# amplifier-controller.net
KiCad netlist of a schematic drawn in EAGLE
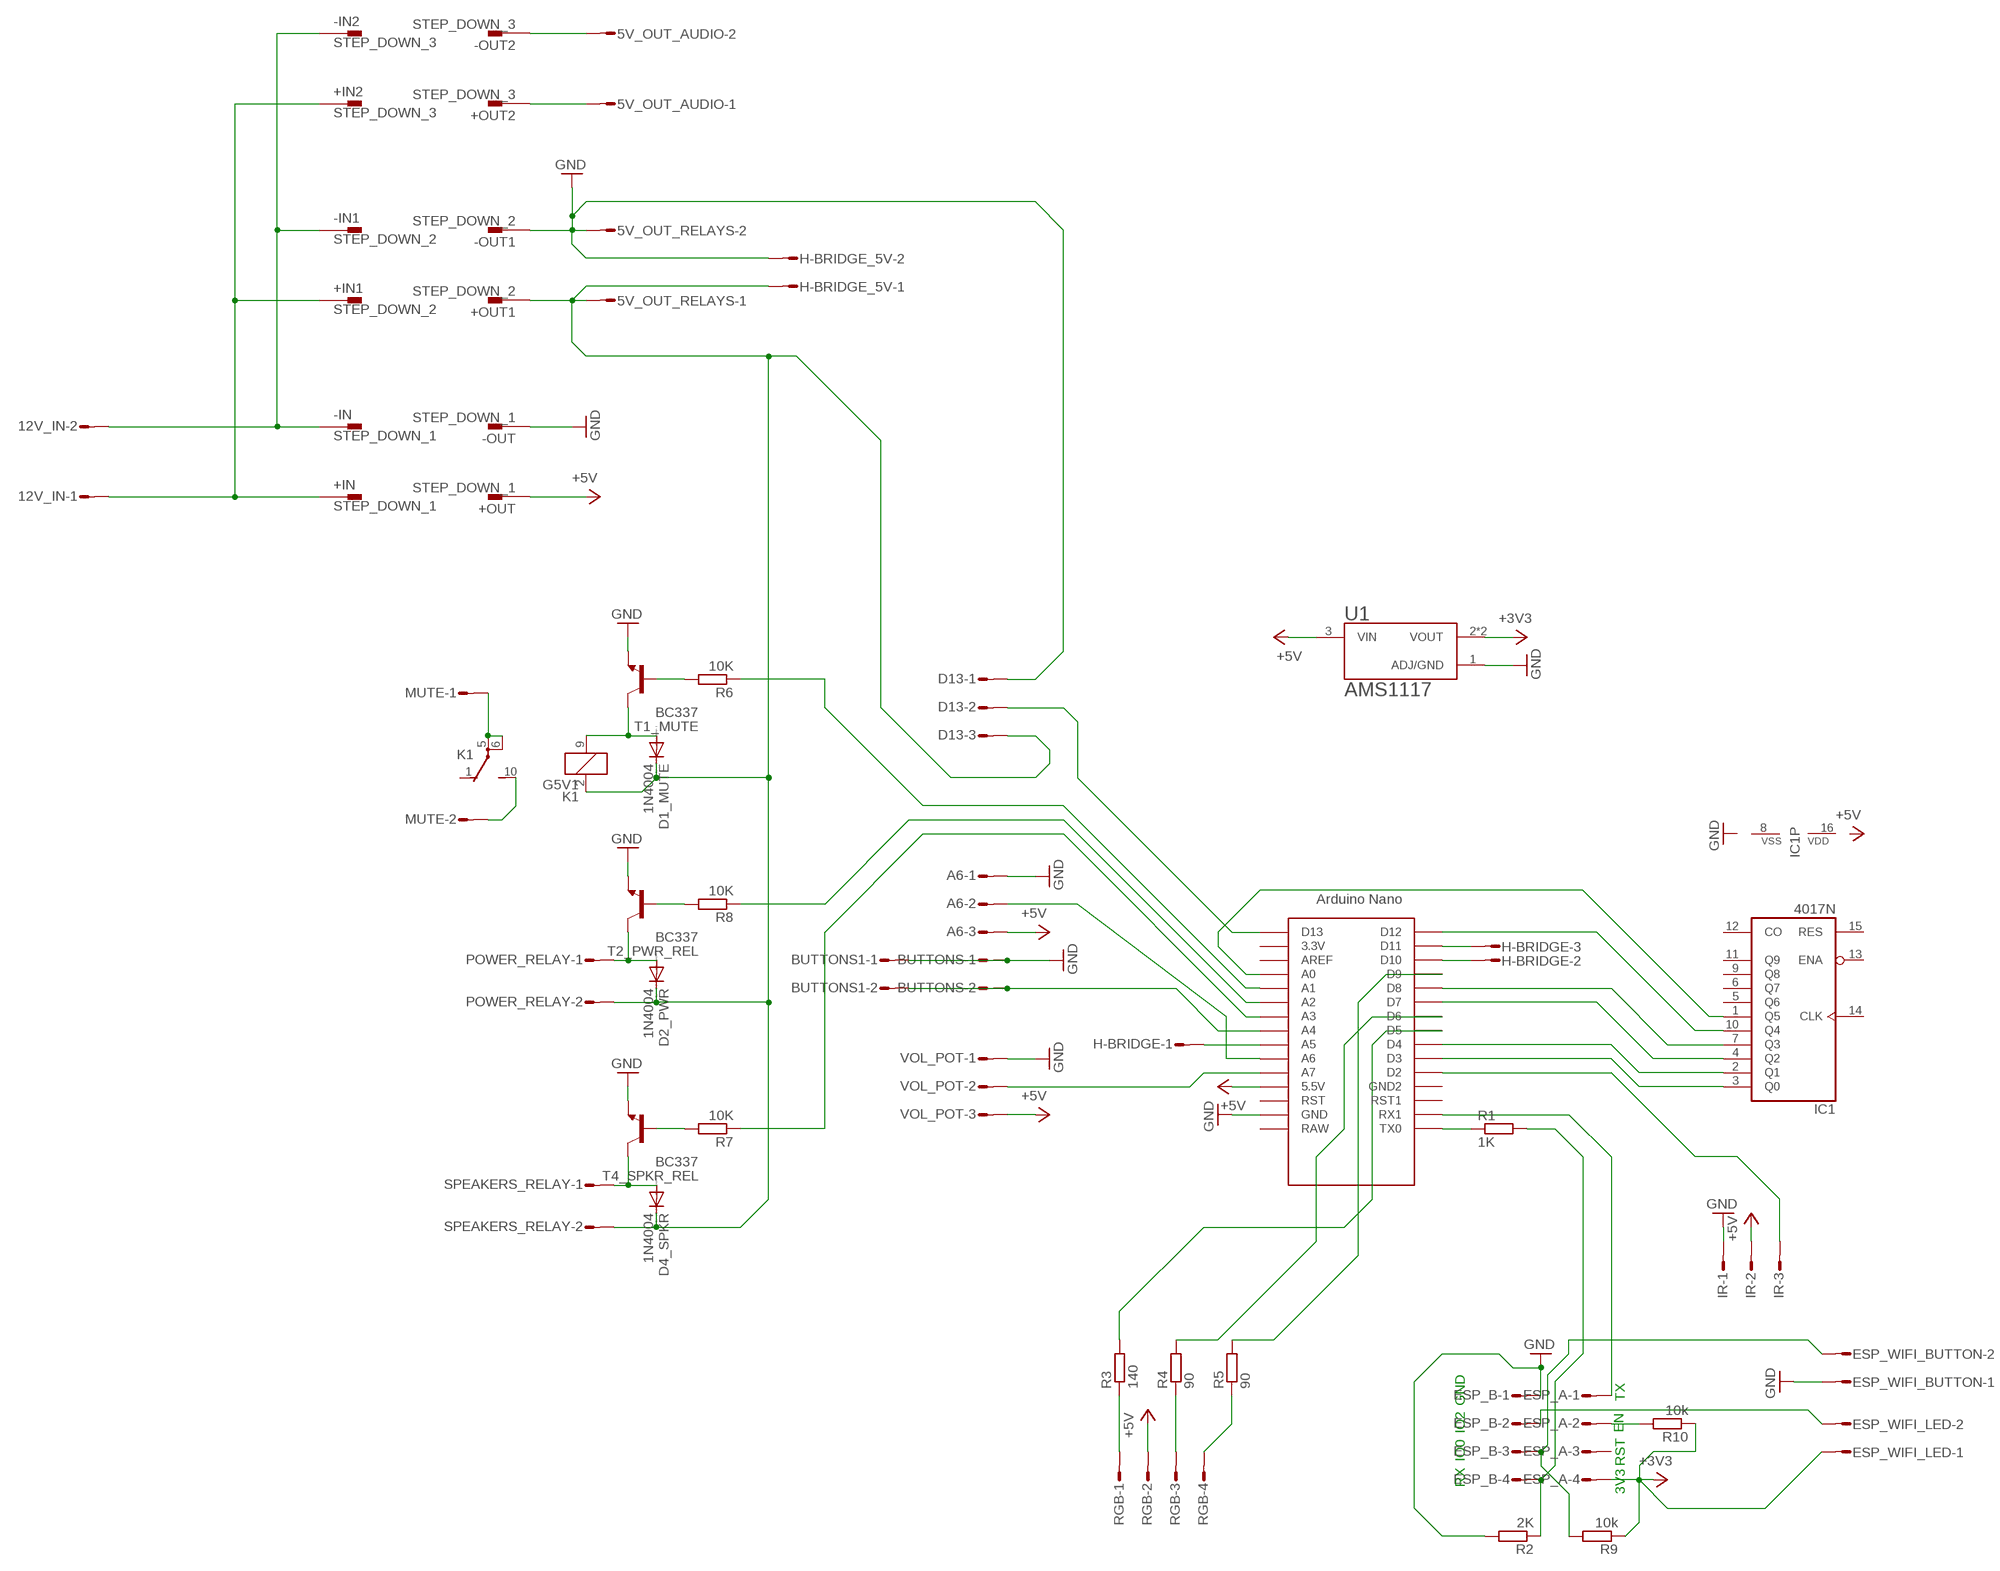
[diagram p0: schematic, sheet 1]

(export (version "E")
  (design (tool "Eeschema 10.0.6"))
  (components
    (comp (ref "+IN")
      (value "STEP_DOWN_1")
      (footprint "eagle-import:62221")
      (fields (field (name "MF") "TYCO ELECTRONICS") (field (name "MPN") "62221-1"))
      (libsource (lib "eagle-import") (part "PIN1-2"))
    )
    (comp (ref "+IN1")
      (value "STEP_DOWN_2")
      (footprint "eagle-import:62221")
      (fields (field (name "MF") "TYCO ELECTRONICS") (field (name "MPN") "62221-1"))
      (libsource (lib "eagle-import") (part "PIN1-2"))
    )
    (comp (ref "+IN2")
      (value "STEP_DOWN_3")
      (footprint "eagle-import:62221")
      (fields (field (name "MF") "TYCO ELECTRONICS") (field (name "MPN") "62221-1"))
      (libsource (lib "eagle-import") (part "PIN1-2"))
    )
    (comp (ref "+OUT")
      (value "STEP_DOWN_1")
      (footprint "eagle-import:62221")
      (fields (field (name "MF") "TYCO ELECTRONICS") (field (name "MPN") "62221-1"))
      (libsource (lib "eagle-import") (part "PIN1-2"))
    )
    (comp (ref "+OUT1")
      (value "STEP_DOWN_2")
      (footprint "eagle-import:62221")
      (fields (field (name "MF") "TYCO ELECTRONICS") (field (name "MPN") "62221-1"))
      (libsource (lib "eagle-import") (part "PIN1-2"))
    )
    (comp (ref "+OUT2")
      (value "STEP_DOWN_3")
      (footprint "eagle-import:62221")
      (fields (field (name "MF") "TYCO ELECTRONICS") (field (name "MPN") "62221-1"))
      (libsource (lib "eagle-import") (part "PIN1-2"))
    )
    (comp (ref "-IN")
      (value "STEP_DOWN_1")
      (footprint "eagle-import:62221")
      (fields (field (name "MF") "TYCO ELECTRONICS") (field (name "MPN") "62221-1"))
      (libsource (lib "eagle-import") (part "PIN1-2"))
    )
    (comp (ref "-IN1")
      (value "STEP_DOWN_2")
      (footprint "eagle-import:62221")
      (fields (field (name "MF") "TYCO ELECTRONICS") (field (name "MPN") "62221-1"))
      (libsource (lib "eagle-import") (part "PIN1-2"))
    )
    (comp (ref "-IN2")
      (value "STEP_DOWN_3")
      (footprint "eagle-import:62221")
      (fields (field (name "MF") "TYCO ELECTRONICS") (field (name "MPN") "62221-1"))
      (libsource (lib "eagle-import") (part "PIN1-2"))
    )
    (comp (ref "-OUT")
      (value "STEP_DOWN_1")
      (footprint "eagle-import:62221")
      (fields (field (name "MF") "TYCO ELECTRONICS") (field (name "MPN") "62221-1"))
      (libsource (lib "eagle-import") (part "PIN1-2"))
    )
    (comp (ref "-OUT1")
      (value "STEP_DOWN_2")
      (footprint "eagle-import:62221")
      (fields (field (name "MF") "TYCO ELECTRONICS") (field (name "MPN") "62221-1"))
      (libsource (lib "eagle-import") (part "PIN1-2"))
    )
    (comp (ref "-OUT2")
      (value "STEP_DOWN_3")
      (footprint "eagle-import:62221")
      (fields (field (name "MF") "TYCO ELECTRONICS") (field (name "MPN") "62221-1"))
      (libsource (lib "eagle-import") (part "PIN1-2"))
    )
    (comp (ref "5V_OUT_AUDIO")
      (value "L02P")
      (footprint "eagle-import:L02P")
      (libsource (lib "eagle-import") (part "L02P"))
    )
    (comp (ref "5V_OUT_RELAYS")
      (value "L02P")
      (footprint "eagle-import:L02P")
      (libsource (lib "eagle-import") (part "L02P"))
    )
    (comp (ref "12V_IN")
      (value "L02P")
      (footprint "eagle-import:L02P")
      (libsource (lib "eagle-import") (part "L02P"))
    )
    (comp (ref "A6")
      (value "L03P")
      (footprint "eagle-import:L03P")
      (libsource (lib "eagle-import") (part "L03P"))
    )
    (comp (ref "BUTTONS")
      (value "L02P")
      (footprint "eagle-import:L02P")
      (libsource (lib "eagle-import") (part "L02P"))
    )
    (comp (ref "BUTTONS1")
      (value "L02P")
      (footprint "eagle-import:L02P")
      (libsource (lib "eagle-import") (part "L02P"))
    )
    (comp (ref "D1_MUTE")
      (value "1N4004")
      (footprint "eagle-import:DO41-10")
      (libsource (lib "eagle-import") (part "1N4004"))
    )
    (comp (ref "D2_PWR")
      (value "1N4004")
      (footprint "eagle-import:DO41-10")
      (libsource (lib "eagle-import") (part "1N4004"))
    )
    (comp (ref "D4_SPKR")
      (value "1N4004")
      (footprint "eagle-import:DO41-10")
      (libsource (lib "eagle-import") (part "1N4004"))
    )
    (comp (ref "D13")
      (value "L03P")
      (footprint "eagle-import:L03P")
      (libsource (lib "eagle-import") (part "L03P"))
    )
    (comp (ref "ESP_A")
      (value "L04P")
      (footprint "eagle-import:L04P")
      (libsource (lib "eagle-import") (part "L04P"))
    )
    (comp (ref "ESP_B")
      (value "L04P")
      (footprint "eagle-import:L04P")
      (libsource (lib "eagle-import") (part "L04P"))
    )
    (comp (ref "ESP_WIFI_BUTTON")
      (value "L02P")
      (footprint "eagle-import:L02P")
      (libsource (lib "eagle-import") (part "L02P"))
    )
    (comp (ref "ESP_WIFI_LED")
      (value "L02P")
      (footprint "eagle-import:L02P")
      (libsource (lib "eagle-import") (part "L02P"))
    )
    (comp (ref "H-BRIDGE")
      (value "L03P")
      (footprint "eagle-import:L03P")
      (libsource (lib "eagle-import") (part "L03P"))
    )
    (comp (ref "H-BRIDGE_5V")
      (value "L02P")
      (footprint "eagle-import:L02P")
      (libsource (lib "eagle-import") (part "L02P"))
    )
    (comp (ref "IC1")
      (value "4017N")
      (footprint "eagle-import:DIL16")
      (libsource (lib "eagle-import") (part "4017N"))
    )
    (comp (ref "IR")
      (value "L03P")
      (footprint "eagle-import:L03P")
      (libsource (lib "eagle-import") (part "L03P"))
    )
    (comp (ref "K1")
      (value "G5V1")
      (footprint "eagle-import:G5V1")
      (fields (field (name "MPN") "G5V-1-DC24"))
      (libsource (lib "eagle-import") (part "G5V1"))
    )
    (comp (ref "MUTE")
      (value "L02P")
      (footprint "eagle-import:L02P")
      (libsource (lib "eagle-import") (part "L02P"))
    )
    (comp (ref "POWER_RELAY")
      (value "L02P")
      (footprint "eagle-import:L02P")
      (libsource (lib "eagle-import") (part "L02P"))
    )
    (comp (ref "R1")
      (value "1K")
      (footprint "eagle-import:0411_15")
      (libsource (lib "eagle-import") (part "resistor_R-EU_0411/15"))
    )
    (comp (ref "R2")
      (value "2K")
      (footprint "eagle-import:0411_15")
      (libsource (lib "eagle-import") (part "resistor_R-EU_0411/15"))
    )
    (comp (ref "R3")
      (value "140")
      (footprint "eagle-import:0411_15")
      (libsource (lib "eagle-import") (part "resistor_R-EU_0411/15"))
    )
    (comp (ref "R4")
      (value "90")
      (footprint "eagle-import:0411_15")
      (libsource (lib "eagle-import") (part "resistor_R-EU_0411/15"))
    )
    (comp (ref "R5")
      (value "90")
      (footprint "eagle-import:0411_15")
      (libsource (lib "eagle-import") (part "resistor_R-EU_0411/15"))
    )
    (comp (ref "R6")
      (value "10K")
      (footprint "eagle-import:0309_12")
      (libsource (lib "eagle-import") (part "resistor_R-EU_0309/12"))
    )
    (comp (ref "R7")
      (value "10K")
      (footprint "eagle-import:0617_22")
      (libsource (lib "eagle-import") (part "R-EU_0617/22"))
    )
    (comp (ref "R8")
      (value "10K")
      (footprint "eagle-import:0309_12")
      (libsource (lib "eagle-import") (part "resistor_R-EU_0309/12"))
    )
    (comp (ref "R9")
      (value "10k")
      (footprint "eagle-import:0411_15")
      (libsource (lib "eagle-import") (part "resistor_R-EU_0411/15"))
    )
    (comp (ref "R10")
      (value "10k")
      (footprint "eagle-import:0411_15")
      (libsource (lib "eagle-import") (part "resistor_R-EU_0411/15"))
    )
    (comp (ref "RGB")
      (value "L04P")
      (footprint "eagle-import:L04P")
      (libsource (lib "eagle-import") (part "L04P"))
    )
    (comp (ref "SPEAKERS_RELAY")
      (value "L02P")
      (footprint "eagle-import:L02P")
      (libsource (lib "eagle-import") (part "L02P"))
    )
    (comp (ref "T1_MUTE")
      (value "BC337")
      (footprint "eagle-import:TO92")
      (libsource (lib "eagle-import") (part "BC337"))
    )
    (comp (ref "T2_PWR_REL")
      (value "BC337")
      (footprint "eagle-import:TO92")
      (libsource (lib "eagle-import") (part "BC337"))
    )
    (comp (ref "T4_SPKR_REL")
      (value "BC337")
      (footprint "eagle-import:TO92")
      (libsource (lib "eagle-import") (part "BC337"))
    )
    (comp (ref "U$1")
      (value "NANO")
      (footprint "eagle-import:NANO")
      (libsource (lib "eagle-import") (part "NANO"))
    )
    (comp (ref "U1")
      (value "AMS1117")
      (footprint "eagle-import:SOT229P700X180-4N")
      (fields (field (name "MF") "Advanced Monolithic Systems"))
      (libsource (lib "eagle-import") (part "AMS1117"))
    )
    (comp (ref "VOL_POT")
      (value "L03P")
      (footprint "eagle-import:L03P")
      (libsource (lib "eagle-import") (part "L03P"))
    )
  )
  (nets
    (net (code "1") (name "+3V3") (class "Default")
      (node (ref "ESP_A") (pin "4") (pinfunction "S_4") (pintype "passive"))
      (node (ref "ESP_WIFI_LED") (pin "1") (pinfunction "S_1") (pintype "passive"))
      (node (ref "R10") (pin "1") (pinfunction "1_1") (pintype "passive"))
      (node (ref "R9") (pin "1") (pinfunction "1_1") (pintype "passive"))
      (node (ref "U1") (pin "2") (pinfunction "VOUT_2") (pintype "output"))
      (node (ref "U1") (pin "4") (pinfunction "VOUT_4") (pintype "output"))
    )
    (net (code "2") (name "+5V") (class "Default")
      (node (ref "+OUT") (pin "1") (pinfunction "1_1") (pintype "passive"))
      (node (ref "A6") (pin "3") (pinfunction "S_3") (pintype "passive"))
      (node (ref "IR") (pin "2") (pinfunction "S_2") (pintype "passive"))
      (node (ref "RGB") (pin "2") (pinfunction "S_2") (pintype "passive"))
      (node (ref "U$1") (pin "5V") (pinfunction "5.5V_5V") (pintype "bidirectional"))
      (node (ref "U1") (pin "3") (pinfunction "VIN_3") (pintype "input"))
      (node (ref "VOL_POT") (pin "3") (pinfunction "S_3") (pintype "passive"))
    )
    (net (code "3") (name "/VDD") (class "Default")
      (node (ref "IC1") (pin "16") (pinfunction "VDD_16") (pintype "power_in"))
    )
    (net (code "4") (name "/VSS") (class "Default")
      (node (ref "IC1") (pin "8") (pinfunction "VSS_8") (pintype "power_in"))
    )
    (net (code "5") (name "GND") (class "Default")
      (node (ref "-OUT") (pin "1") (pinfunction "1_1") (pintype "passive"))
      (node (ref "-OUT1") (pin "1") (pinfunction "1_1") (pintype "passive"))
      (node (ref "5V_OUT_RELAYS") (pin "2") (pinfunction "S_2") (pintype "passive"))
      (node (ref "A6") (pin "1") (pinfunction "S_1") (pintype "passive"))
      (node (ref "BUTTONS") (pin "1") (pinfunction "S_1") (pintype "passive"))
      (node (ref "BUTTONS1") (pin "1") (pinfunction "S_1") (pintype "passive"))
      (node (ref "D13") (pin "1") (pinfunction "S_1") (pintype "passive"))
      (node (ref "ESP_B") (pin "1") (pinfunction "S_1") (pintype "passive"))
      (node (ref "ESP_WIFI_BUTTON") (pin "1") (pinfunction "S_1") (pintype "passive"))
      (node (ref "H-BRIDGE_5V") (pin "2") (pinfunction "S_2") (pintype "passive"))
      (node (ref "IR") (pin "1") (pinfunction "S_1") (pintype "passive"))
      (node (ref "R2") (pin "2") (pinfunction "2_2") (pintype "passive"))
      (node (ref "T1_MUTE") (pin "1") (pinfunction "E_1") (pintype "passive"))
      (node (ref "T2_PWR_REL") (pin "1") (pinfunction "E_1") (pintype "passive"))
      (node (ref "T4_SPKR_REL") (pin "1") (pinfunction "E_1") (pintype "passive"))
      (node (ref "U$1") (pin "GND") (pinfunction "GND_GND") (pintype "bidirectional"))
      (node (ref "U1") (pin "1") (pinfunction "ADJ/GND_1") (pintype "power_in"))
      (node (ref "VOL_POT") (pin "1") (pinfunction "S_1") (pintype "passive"))
    )
    (net (code "6") (name "Net-(5V_OUT_AUDIOA-S)") (class "Default")
      (node (ref "+OUT2") (pin "1") (pinfunction "1_1") (pintype "passive"))
      (node (ref "5V_OUT_AUDIO") (pin "1") (pinfunction "S_1") (pintype "passive"))
    )
    (net (code "7") (name "Net-(5V_OUT_AUDIOB-S)") (class "Default")
      (node (ref "-OUT2") (pin "1") (pinfunction "1_1") (pintype "passive"))
      (node (ref "5V_OUT_AUDIO") (pin "2") (pinfunction "S_2") (pintype "passive"))
    )
    (net (code "8") (name "Net-(5V_OUT_RELAYSA-S)") (class "Default")
      (node (ref "+OUT1") (pin "1") (pinfunction "1_1") (pintype "passive"))
      (node (ref "5V_OUT_RELAYS") (pin "1") (pinfunction "S_1") (pintype "passive"))
      (node (ref "D13") (pin "3") (pinfunction "S_3") (pintype "passive"))
      (node (ref "D1_MUTE") (pin "C") (pinfunction "C_C") (pintype "passive"))
      (node (ref "D2_PWR") (pin "C") (pinfunction "C_C") (pintype "passive"))
      (node (ref "D4_SPKR") (pin "C") (pinfunction "C_C") (pintype "passive"))
      (node (ref "H-BRIDGE_5V") (pin "1") (pinfunction "S_1") (pintype "passive"))
      (node (ref "K1") (pin "2") (pinfunction "1_2") (pintype "passive"))
      (node (ref "POWER_RELAY") (pin "2") (pinfunction "S_2") (pintype "passive"))
      (node (ref "SPEAKERS_RELAY") (pin "2") (pinfunction "S_2") (pintype "passive"))
    )
    (net (code "9") (name "Net-(12V_INA-S)") (class "Default")
      (node (ref "+IN") (pin "1") (pinfunction "1_1") (pintype "passive"))
      (node (ref "+IN1") (pin "1") (pinfunction "1_1") (pintype "passive"))
      (node (ref "+IN2") (pin "1") (pinfunction "1_1") (pintype "passive"))
      (node (ref "12V_IN") (pin "1") (pinfunction "S_1") (pintype "passive"))
    )
    (net (code "10") (name "Net-(12V_INB-S)") (class "Default")
      (node (ref "-IN") (pin "1") (pinfunction "1_1") (pintype "passive"))
      (node (ref "-IN1") (pin "1") (pinfunction "1_1") (pintype "passive"))
      (node (ref "-IN2") (pin "1") (pinfunction "1_1") (pintype "passive"))
      (node (ref "12V_IN") (pin "2") (pinfunction "S_2") (pintype "passive"))
    )
    (net (code "11") (name "Net-(A6B-S)") (class "Default")
      (node (ref "A6") (pin "2") (pinfunction "S_2") (pintype "passive"))
      (node (ref "U$1") (pin "A6") (pinfunction "A6_A6") (pintype "bidirectional"))
    )
    (net (code "12") (name "Net-(BUTTONS1B-S)") (class "Default")
      (node (ref "BUTTONS") (pin "2") (pinfunction "S_2") (pintype "passive"))
      (node (ref "BUTTONS1") (pin "2") (pinfunction "S_2") (pintype "passive"))
      (node (ref "U$1") (pin "A4") (pinfunction "A4_A4") (pintype "bidirectional"))
    )
    (net (code "13") (name "Net-(D13B-S)") (class "Default")
      (node (ref "D13") (pin "2") (pinfunction "S_2") (pintype "passive"))
      (node (ref "U$1") (pin "D13") (pinfunction "D13_D13") (pintype "bidirectional"))
    )
    (net (code "14") (name "Net-(ESP_AA-S)") (class "Default")
      (node (ref "ESP_A") (pin "1") (pinfunction "S_1") (pintype "passive"))
      (node (ref "U$1") (pin "RX1") (pinfunction "RX1_RX1") (pintype "bidirectional"))
    )
    (net (code "15") (name "Net-(ESP_AB-S)") (class "Default")
      (node (ref "ESP_A") (pin "2") (pinfunction "S_2") (pintype "passive"))
      (node (ref "R10") (pin "2") (pinfunction "2_2") (pintype "passive"))
    )
    (net (code "16") (name "Net-(ESP_BB-S)") (class "Default")
      (node (ref "ESP_B") (pin "2") (pinfunction "S_2") (pintype "passive"))
      (node (ref "ESP_WIFI_LED") (pin "2") (pinfunction "S_2") (pintype "passive"))
    )
    (net (code "17") (name "Net-(ESP_BC-S)") (class "Default")
      (node (ref "ESP_B") (pin "3") (pinfunction "S_3") (pintype "passive"))
      (node (ref "ESP_WIFI_BUTTON") (pin "2") (pinfunction "S_2") (pintype "passive"))
      (node (ref "R9") (pin "2") (pinfunction "2_2") (pintype "passive"))
    )
    (net (code "18") (name "Net-(ESP_BD-S)") (class "Default")
      (node (ref "ESP_B") (pin "4") (pinfunction "S_4") (pintype "passive"))
      (node (ref "R1") (pin "2") (pinfunction "2_2") (pintype "passive"))
      (node (ref "R2") (pin "1") (pinfunction "1_1") (pintype "passive"))
    )
    (net (code "19") (name "Net-(H-BRIDGEA-S)") (class "Default")
      (node (ref "H-BRIDGE") (pin "1") (pinfunction "S_1") (pintype "passive"))
      (node (ref "U$1") (pin "A5") (pinfunction "A5_A5") (pintype "bidirectional"))
    )
    (net (code "20") (name "Net-(H-BRIDGEB-S)") (class "Default")
      (node (ref "H-BRIDGE") (pin "2") (pinfunction "S_2") (pintype "passive"))
      (node (ref "U$1") (pin "D10") (pinfunction "D10_D10") (pintype "bidirectional"))
    )
    (net (code "21") (name "Net-(H-BRIDGEC-S)") (class "Default")
      (node (ref "H-BRIDGE") (pin "3") (pinfunction "S_3") (pintype "passive"))
      (node (ref "U$1") (pin "D11") (pinfunction "D11_D11") (pintype "bidirectional"))
    )
    (net (code "22") (name "Net-(IC1A-Q0)") (class "Default")
      (node (ref "IC1") (pin "3") (pinfunction "Q0_3") (pintype "output"))
      (node (ref "U$1") (pin "D3") (pinfunction "D3_D3") (pintype "bidirectional"))
    )
    (net (code "23") (name "Net-(IC1A-Q1)") (class "Default")
      (node (ref "IC1") (pin "2") (pinfunction "Q1_2") (pintype "output"))
      (node (ref "U$1") (pin "D4") (pinfunction "D4_D4") (pintype "bidirectional"))
    )
    (net (code "24") (name "Net-(IC1A-Q2)") (class "Default")
      (node (ref "IC1") (pin "4") (pinfunction "Q2_4") (pintype "output"))
      (node (ref "U$1") (pin "D7") (pinfunction "D7_D7") (pintype "bidirectional"))
    )
    (net (code "25") (name "Net-(IC1A-Q3)") (class "Default")
      (node (ref "IC1") (pin "7") (pinfunction "Q3_7") (pintype "output"))
      (node (ref "U$1") (pin "D8") (pinfunction "D8_D8") (pintype "bidirectional"))
    )
    (net (code "26") (name "Net-(IC1A-Q4)") (class "Default")
      (node (ref "IC1") (pin "10") (pinfunction "Q4_10") (pintype "output"))
      (node (ref "U$1") (pin "D12") (pinfunction "D12_D12") (pintype "bidirectional"))
    )
    (net (code "27") (name "Net-(IC1A-Q5)") (class "Default")
      (node (ref "IC1") (pin "1") (pinfunction "Q5_1") (pintype "output"))
      (node (ref "U$1") (pin "A0") (pinfunction "A0_A0") (pintype "bidirectional"))
    )
    (net (code "28") (name "Net-(IRC-S)") (class "Default")
      (node (ref "IR") (pin "3") (pinfunction "S_3") (pintype "passive"))
      (node (ref "U$1") (pin "D2") (pinfunction "D2_D2") (pintype "bidirectional"))
    )
    (net (code "29") (name "Net-(K1A-2)") (class "Default")
      (node (ref "D1_MUTE") (pin "A") (pinfunction "A_A") (pintype "passive"))
      (node (ref "K1") (pin "9") (pinfunction "2_9") (pintype "passive"))
      (node (ref "T1_MUTE") (pin "3") (pinfunction "C_3") (pintype "passive"))
    )
    (net (code "30") (name "Net-(K1B-S)") (class "Default")
      (node (ref "K1") (pin "10") (pinfunction "S_10") (pintype "passive"))
      (node (ref "MUTE") (pin "2") (pinfunction "S_2") (pintype "passive"))
    )
    (net (code "31") (name "Net-(MUTEA-S)") (class "Default")
      (node (ref "K1") (pin "5") (pinfunction "P_5") (pintype "passive"))
      (node (ref "K1") (pin "6") (pinfunction "P_6") (pintype "passive"))
      (node (ref "MUTE") (pin "1") (pinfunction "S_1") (pintype "passive"))
    )
    (net (code "32") (name "Net-(POWER_RELAYA-S)") (class "Default")
      (node (ref "D2_PWR") (pin "A") (pinfunction "A_A") (pintype "passive"))
      (node (ref "POWER_RELAY") (pin "1") (pinfunction "S_1") (pintype "passive"))
      (node (ref "T2_PWR_REL") (pin "3") (pinfunction "C_3") (pintype "passive"))
    )
    (net (code "33") (name "Net-(R1-Pad1)") (class "Default")
      (node (ref "R1") (pin "1") (pinfunction "1_1") (pintype "passive"))
      (node (ref "U$1") (pin "TX0") (pinfunction "TX0_TX0") (pintype "bidirectional"))
    )
    (net (code "34") (name "Net-(R3-Pad2)") (class "Default")
      (node (ref "R3") (pin "2") (pinfunction "2_2") (pintype "passive"))
      (node (ref "U$1") (pin "D5") (pinfunction "D5_D5") (pintype "bidirectional"))
    )
    (net (code "35") (name "Net-(R4-Pad2)") (class "Default")
      (node (ref "R4") (pin "2") (pinfunction "2_2") (pintype "passive"))
      (node (ref "U$1") (pin "D6") (pinfunction "D6_D6") (pintype "bidirectional"))
    )
    (net (code "36") (name "Net-(R5-Pad2)") (class "Default")
      (node (ref "R5") (pin "2") (pinfunction "2_2") (pintype "passive"))
      (node (ref "U$1") (pin "D9") (pinfunction "D9_D9") (pintype "bidirectional"))
    )
    (net (code "37") (name "Net-(R6-Pad1)") (class "Default")
      (node (ref "R6") (pin "1") (pinfunction "1_1") (pintype "passive"))
      (node (ref "U$1") (pin "A1") (pinfunction "A1_A1") (pintype "bidirectional"))
    )
    (net (code "38") (name "Net-(R7-Pad1)") (class "Default")
      (node (ref "R7") (pin "1") (pinfunction "1_1") (pintype "passive"))
      (node (ref "U$1") (pin "A3") (pinfunction "A3_A3") (pintype "bidirectional"))
    )
    (net (code "39") (name "Net-(R8-Pad1)") (class "Default")
      (node (ref "R8") (pin "1") (pinfunction "1_1") (pintype "passive"))
      (node (ref "U$1") (pin "A2") (pinfunction "A2_A2") (pintype "bidirectional"))
    )
    (net (code "40") (name "Net-(RGBA-S)") (class "Default")
      (node (ref "R3") (pin "1") (pinfunction "1_1") (pintype "passive"))
      (node (ref "RGB") (pin "1") (pinfunction "S_1") (pintype "passive"))
    )
    (net (code "41") (name "Net-(RGBC-S)") (class "Default")
      (node (ref "R4") (pin "1") (pinfunction "1_1") (pintype "passive"))
      (node (ref "RGB") (pin "3") (pinfunction "S_3") (pintype "passive"))
    )
    (net (code "42") (name "Net-(RGBD-S)") (class "Default")
      (node (ref "R5") (pin "1") (pinfunction "1_1") (pintype "passive"))
      (node (ref "RGB") (pin "4") (pinfunction "S_4") (pintype "passive"))
    )
    (net (code "43") (name "Net-(SPEAKERS_RELAYA-S)") (class "Default")
      (node (ref "D4_SPKR") (pin "A") (pinfunction "A_A") (pintype "passive"))
      (node (ref "SPEAKERS_RELAY") (pin "1") (pinfunction "S_1") (pintype "passive"))
      (node (ref "T4_SPKR_REL") (pin "3") (pinfunction "C_3") (pintype "passive"))
    )
    (net (code "44") (name "Net-(T1_MUTE-B)") (class "Default")
      (node (ref "R6") (pin "2") (pinfunction "2_2") (pintype "passive"))
      (node (ref "T1_MUTE") (pin "2") (pinfunction "B_2") (pintype "passive"))
    )
    (net (code "45") (name "Net-(T2_PWR_REL-B)") (class "Default")
      (node (ref "R8") (pin "2") (pinfunction "2_2") (pintype "passive"))
      (node (ref "T2_PWR_REL") (pin "2") (pinfunction "B_2") (pintype "passive"))
    )
    (net (code "46") (name "Net-(T4_SPKR_REL-B)") (class "Default")
      (node (ref "R7") (pin "2") (pinfunction "2_2") (pintype "passive"))
      (node (ref "T4_SPKR_REL") (pin "2") (pinfunction "B_2") (pintype "passive"))
    )
    (net (code "47") (name "Net-(VOL_POTB-S)") (class "Default")
      (node (ref "U$1") (pin "A7") (pinfunction "A7_A7") (pintype "bidirectional"))
      (node (ref "VOL_POT") (pin "2") (pinfunction "S_2") (pintype "passive"))
    )
    (net (code "48") (name "unconnected-(ESP_AC-S-Pad3)") (class "Default")
      (node (ref "ESP_A") (pin "3") (pinfunction "S_3") (pintype "passive"))
    )
    (net (code "49") (name "unconnected-(IC1A-CLK-Pad14)") (class "Default")
      (node (ref "IC1") (pin "14") (pinfunction "CLK_14") (pintype "input"))
    )
    (net (code "50") (name "unconnected-(IC1A-CO-Pad12)") (class "Default")
      (node (ref "IC1") (pin "12") (pinfunction "CO_12") (pintype "output"))
    )
    (net (code "51") (name "unconnected-(IC1A-ENA-Pad13)") (class "Default")
      (node (ref "IC1") (pin "13") (pinfunction "ENA_13") (pintype "input"))
    )
    (net (code "52") (name "unconnected-(IC1A-Q6-Pad5)") (class "Default")
      (node (ref "IC1") (pin "5") (pinfunction "Q6_5") (pintype "output"))
    )
    (net (code "53") (name "unconnected-(IC1A-Q7-Pad6)") (class "Default")
      (node (ref "IC1") (pin "6") (pinfunction "Q7_6") (pintype "output"))
    )
    (net (code "54") (name "unconnected-(IC1A-Q8-Pad9)") (class "Default")
      (node (ref "IC1") (pin "9") (pinfunction "Q8_9") (pintype "output"))
    )
    (net (code "55") (name "unconnected-(IC1A-Q9-Pad11)") (class "Default")
      (node (ref "IC1") (pin "11") (pinfunction "Q9_11") (pintype "output"))
    )
    (net (code "56") (name "unconnected-(IC1A-RES-Pad15)") (class "Default")
      (node (ref "IC1") (pin "15") (pinfunction "RES_15") (pintype "input"))
    )
    (net (code "57") (name "unconnected-(K1B-O-Pad1)") (class "Default")
      (node (ref "K1") (pin "1") (pinfunction "O_1") (pintype "passive"))
    )
    (net (code "58") (name "unconnected-(U$1-GND2-PadGND1)") (class "Default")
      (node (ref "U$1") (pin "GND1") (pinfunction "GND2_GND1") (pintype "bidirectional"))
    )
    (net (code "59") (name "unconnected-(U$1-Pad3.3V)") (class "Default")
      (node (ref "U$1") (pin "3.3V") (pinfunction "3.3V_3.3V") (pintype "bidirectional"))
    )
    (net (code "60") (name "unconnected-(U$1-PadAREF)") (class "Default")
      (node (ref "U$1") (pin "AREF") (pinfunction "AREF_AREF") (pintype "bidirectional"))
    )
    (net (code "61") (name "unconnected-(U$1-PadRAW)") (class "Default")
      (node (ref "U$1") (pin "RAW") (pinfunction "RAW_RAW") (pintype "bidirectional"))
    )
    (net (code "62") (name "unconnected-(U$1-PadRST)") (class "Default")
      (node (ref "U$1") (pin "RST") (pinfunction "RST_RST") (pintype "bidirectional"))
    )
    (net (code "63") (name "unconnected-(U$1-PadRST1)") (class "Default")
      (node (ref "U$1") (pin "RST1") (pinfunction "RST1_RST1") (pintype "bidirectional"))
    )
  )
)
